# 1-Schematic_RpiZeroKeyboard.net
KiCad netlist of a schematic drawn in EasyEDA
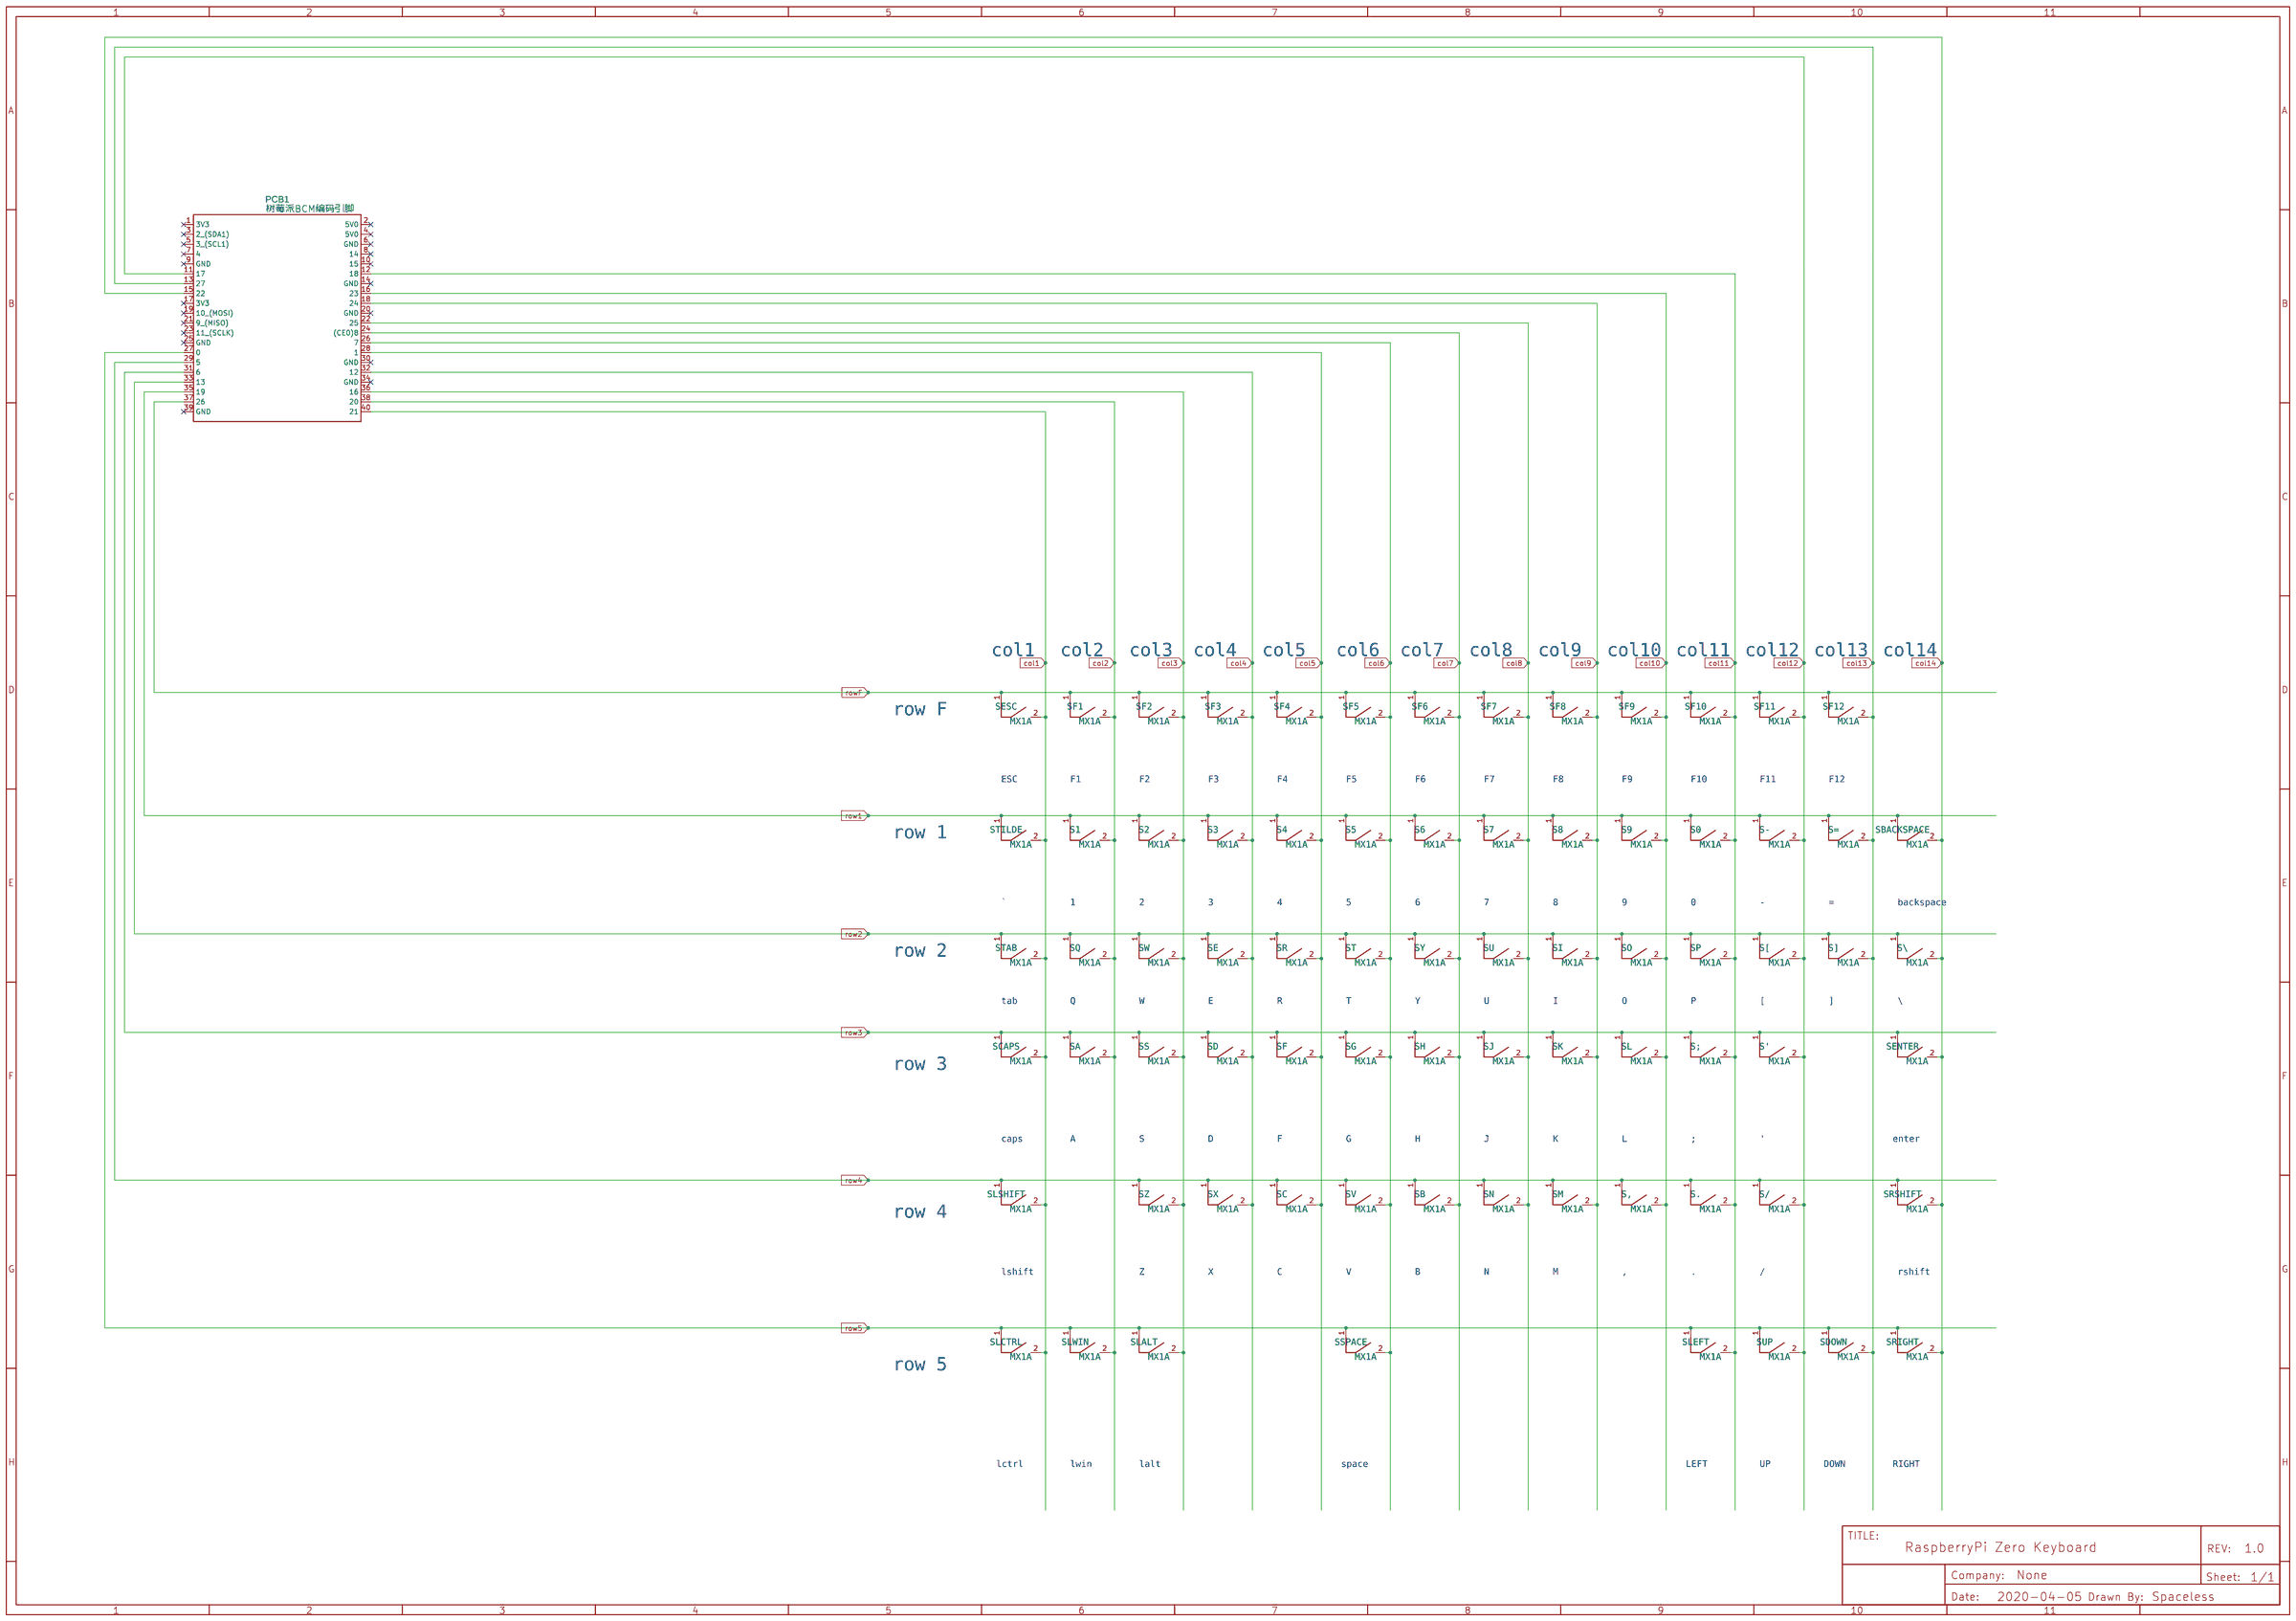
[diagram p0: schematic sheet]

(export (version "E")
  (design (tool "Eeschema 10.0.6"))
  (components
    (comp (ref "PCB1") (value "树莓派BCM编码引脚") (libsource (lib "") (part "树莓派 zero w BCM编码引脚")))
    (comp (ref "S'") (value "MX1A") (libsource (lib "") (part "Unknown_1800_275")))
    (comp (ref "S,") (value "MX1A") (libsource (lib "") (part "Unknown_1660_425")))
    (comp (ref "S-") (value "MX1A") (libsource (lib "") (part "Unknown_1800_55")))
    (comp (ref "S.") (value "MX1A") (libsource (lib "") (part "Unknown_1730_425")))
    (comp (ref "S/") (value "MX1A") (libsource (lib "") (part "Unknown_1800_425")))
    (comp (ref "S0") (value "MX1A") (libsource (lib "") (part "Unknown_1730_55")))
    (comp (ref "S1") (value "MX1A") (libsource (lib "") (part "Unknown_1100_55")))
    (comp (ref "S2") (value "MX1A") (libsource (lib "") (part "Unknown_1170_55")))
    (comp (ref "S3") (value "MX1A") (libsource (lib "") (part "Unknown_1240_55")))
    (comp (ref "S4") (value "MX1A") (libsource (lib "") (part "Unknown_1310_55")))
    (comp (ref "S5") (value "MX1A") (libsource (lib "") (part "Unknown_1380_55")))
    (comp (ref "S6") (value "MX1A") (libsource (lib "") (part "Unknown_1450_55")))
    (comp (ref "S7") (value "MX1A") (libsource (lib "") (part "Unknown_1520_55")))
    (comp (ref "S8") (value "MX1A") (libsource (lib "") (part "Unknown_1590_55")))
    (comp (ref "S9") (value "MX1A") (libsource (lib "") (part "Unknown_1660_55")))
    (comp (ref "S;") (value "MX1A") (libsource (lib "") (part "Unknown_1730_275")))
    (comp (ref "S=") (value "MX1A") (libsource (lib "") (part "Unknown_1870_55")))
    (comp (ref "SA") (value "MX1A") (libsource (lib "") (part "Unknown_1100_275")))
    (comp (ref "SB") (value "MX1A") (libsource (lib "") (part "Unknown_1450_425")))
    (comp (ref "SBACKSPACE") (value "MX1A") (libsource (lib "") (part "Unknown_1940_55")))
    (comp (ref "SC") (value "MX1A") (libsource (lib "") (part "Unknown_1310_425")))
    (comp (ref "SCAPS") (value "MX1A") (libsource (lib "") (part "Unknown_1030_275")))
    (comp (ref "SD") (value "MX1A") (libsource (lib "") (part "Unknown_1240_275")))
    (comp (ref "SDOWN") (value "MX1A") (libsource (lib "") (part "Unknown_1870_575")))
    (comp (ref "SE") (value "MX1A") (libsource (lib "") (part "Unknown_1240_175")))
    (comp (ref "SENTER") (value "MX1A") (libsource (lib "") (part "Unknown_1940_275")))
    (comp (ref "SESC") (value "MX1A") (libsource (lib "") (part "Unknown_1030_-70")))
    (comp (ref "SF") (value "MX1A") (libsource (lib "") (part "Unknown_1310_275")))
    (comp (ref "SF1") (value "MX1A") (libsource (lib "") (part "Unknown_1100_-70")))
    (comp (ref "SF2") (value "MX1A") (libsource (lib "") (part "Unknown_1170_-70")))
    (comp (ref "SF3") (value "MX1A") (libsource (lib "") (part "Unknown_1240_-70")))
    (comp (ref "SF4") (value "MX1A") (libsource (lib "") (part "Unknown_1310_-70")))
    (comp (ref "SF5") (value "MX1A") (libsource (lib "") (part "Unknown_1380_-70")))
    (comp (ref "SF6") (value "MX1A") (libsource (lib "") (part "Unknown_1450_-70")))
    (comp (ref "SF7") (value "MX1A") (libsource (lib "") (part "Unknown_1520_-70")))
    (comp (ref "SF8") (value "MX1A") (libsource (lib "") (part "Unknown_1590_-70")))
    (comp (ref "SF9") (value "MX1A") (libsource (lib "") (part "Unknown_1660_-70")))
    (comp (ref "SF10") (value "MX1A") (libsource (lib "") (part "Unknown_1730_-70")))
    (comp (ref "SF11") (value "MX1A") (libsource (lib "") (part "Unknown_1800_-70")))
    (comp (ref "SF12") (value "MX1A") (libsource (lib "") (part "Unknown_1870_-70")))
    (comp (ref "SG") (value "MX1A") (libsource (lib "") (part "Unknown_1380_275")))
    (comp (ref "SH") (value "MX1A") (libsource (lib "") (part "Unknown_1450_275")))
    (comp (ref "SI") (value "MX1A") (libsource (lib "") (part "Unknown_1590_175")))
    (comp (ref "SJ") (value "MX1A") (libsource (lib "") (part "Unknown_1520_275")))
    (comp (ref "SK") (value "MX1A") (libsource (lib "") (part "Unknown_1590_275")))
    (comp (ref "SL") (value "MX1A") (libsource (lib "") (part "Unknown_1660_275")))
    (comp (ref "SLALT") (value "MX1A") (libsource (lib "") (part "Unknown_1170_575")))
    (comp (ref "SLCTRL") (value "MX1A") (libsource (lib "") (part "Unknown_1030_575")))
    (comp (ref "SLEFT") (value "MX1A") (libsource (lib "") (part "Unknown_1730_575")))
    (comp (ref "SLSHIFT") (value "MX1A") (libsource (lib "") (part "Unknown_1030_425")))
    (comp (ref "SLWIN") (value "MX1A") (libsource (lib "") (part "Unknown_1100_575")))
    (comp (ref "SM") (value "MX1A") (libsource (lib "") (part "Unknown_1590_425")))
    (comp (ref "SN") (value "MX1A") (libsource (lib "") (part "Unknown_1520_425")))
    (comp (ref "SO") (value "MX1A") (libsource (lib "") (part "Unknown_1660_175")))
    (comp (ref "SP") (value "MX1A") (libsource (lib "") (part "Unknown_1730_175")))
    (comp (ref "SQ") (value "MX1A") (libsource (lib "") (part "Unknown_1100_175")))
    (comp (ref "SR") (value "MX1A") (libsource (lib "") (part "Unknown_1310_175")))
    (comp (ref "SRIGHT") (value "MX1A") (libsource (lib "") (part "Unknown_1940_575")))
    (comp (ref "SRSHIFT") (value "MX1A") (libsource (lib "") (part "Unknown_1940_425")))
    (comp (ref "SS") (value "MX1A") (libsource (lib "") (part "Unknown_1170_275")))
    (comp (ref "SSPACE") (value "MX1A") (libsource (lib "") (part "Unknown_1380_575")))
    (comp (ref "ST") (value "MX1A") (libsource (lib "") (part "Unknown_1380_175")))
    (comp (ref "STAB") (value "MX1A") (libsource (lib "") (part "Unknown_1030_175")))
    (comp (ref "STILDE") (value "MX1A") (libsource (lib "") (part "Unknown_1030_55")))
    (comp (ref "SU") (value "MX1A") (libsource (lib "") (part "Unknown_1520_175")))
    (comp (ref "SUP") (value "MX1A") (libsource (lib "") (part "Unknown_1800_575")))
    (comp (ref "SV") (value "MX1A") (libsource (lib "") (part "Unknown_1380_425")))
    (comp (ref "SW") (value "MX1A") (libsource (lib "") (part "Unknown_1170_175")))
    (comp (ref "SX") (value "MX1A") (libsource (lib "") (part "Unknown_1240_425")))
    (comp (ref "SY") (value "MX1A") (libsource (lib "") (part "Unknown_1450_175")))
    (comp (ref "SZ") (value "MX1A") (libsource (lib "") (part "Unknown_1170_425")))
    (comp (ref "S[") (value "MX1A") (libsource (lib "") (part "Unknown_1800_175")))
    (comp (ref "S\\") (value "MX1A") (libsource (lib "") (part "Unknown_1940_175")))
    (comp (ref "S]") (value "MX1A") (libsource (lib "") (part "Unknown_1870_175")))
  )
  (nets
    (net (code "1") (name "col1") (class "Default")
      (node (ref "PCB1") (pin "40") (pinfunction "21_40") (pintype "unspecified"))
      (node (ref "SCAPS") (pin "2") (pintype "unspecified"))
      (node (ref "SESC") (pin "2") (pintype "unspecified"))
      (node (ref "SLCTRL") (pin "2") (pintype "unspecified"))
      (node (ref "SLSHIFT") (pin "2") (pintype "unspecified"))
      (node (ref "STAB") (pin "2") (pintype "unspecified"))
      (node (ref "STILDE") (pin "2") (pintype "unspecified"))
    )
    (net (code "2") (name "col2") (class "Default")
      (node (ref "PCB1") (pin "38") (pinfunction "20_38") (pintype "unspecified"))
      (node (ref "S1") (pin "2") (pintype "unspecified"))
      (node (ref "SA") (pin "2") (pintype "unspecified"))
      (node (ref "SF1") (pin "2") (pintype "unspecified"))
      (node (ref "SLWIN") (pin "2") (pintype "unspecified"))
      (node (ref "SQ") (pin "2") (pintype "unspecified"))
    )
    (net (code "3") (name "col3") (class "Default")
      (node (ref "PCB1") (pin "36") (pinfunction "16_36") (pintype "unspecified"))
      (node (ref "S2") (pin "2") (pintype "unspecified"))
      (node (ref "SF2") (pin "2") (pintype "unspecified"))
      (node (ref "SLALT") (pin "2") (pintype "unspecified"))
      (node (ref "SS") (pin "2") (pintype "unspecified"))
      (node (ref "SW") (pin "2") (pintype "unspecified"))
      (node (ref "SZ") (pin "2") (pintype "unspecified"))
    )
    (net (code "4") (name "col4") (class "Default")
      (node (ref "PCB1") (pin "32") (pinfunction "12_32") (pintype "unspecified"))
      (node (ref "S3") (pin "2") (pintype "unspecified"))
      (node (ref "SD") (pin "2") (pintype "unspecified"))
      (node (ref "SE") (pin "2") (pintype "unspecified"))
      (node (ref "SF3") (pin "2") (pintype "unspecified"))
      (node (ref "SX") (pin "2") (pintype "unspecified"))
    )
    (net (code "5") (name "col5") (class "Default")
      (node (ref "PCB1") (pin "28") (pinfunction "1_28") (pintype "unspecified"))
      (node (ref "S4") (pin "2") (pintype "unspecified"))
      (node (ref "SC") (pin "2") (pintype "unspecified"))
      (node (ref "SF") (pin "2") (pintype "unspecified"))
      (node (ref "SF4") (pin "2") (pintype "unspecified"))
      (node (ref "SR") (pin "2") (pintype "unspecified"))
    )
    (net (code "6") (name "col6") (class "Default")
      (node (ref "PCB1") (pin "26") (pinfunction "7_26") (pintype "unspecified"))
      (node (ref "S5") (pin "2") (pintype "unspecified"))
      (node (ref "SF5") (pin "2") (pintype "unspecified"))
      (node (ref "SG") (pin "2") (pintype "unspecified"))
      (node (ref "SSPACE") (pin "2") (pintype "unspecified"))
      (node (ref "ST") (pin "2") (pintype "unspecified"))
      (node (ref "SV") (pin "2") (pintype "unspecified"))
    )
    (net (code "7") (name "col7") (class "Default")
      (node (ref "PCB1") (pin "24") (pinfunction "(CE0)8_24") (pintype "unspecified"))
      (node (ref "S6") (pin "2") (pintype "unspecified"))
      (node (ref "SB") (pin "2") (pintype "unspecified"))
      (node (ref "SF6") (pin "2") (pintype "unspecified"))
      (node (ref "SH") (pin "2") (pintype "unspecified"))
      (node (ref "SY") (pin "2") (pintype "unspecified"))
    )
    (net (code "8") (name "col8") (class "Default")
      (node (ref "PCB1") (pin "22") (pinfunction "25_22") (pintype "unspecified"))
      (node (ref "S7") (pin "2") (pintype "unspecified"))
      (node (ref "SF7") (pin "2") (pintype "unspecified"))
      (node (ref "SJ") (pin "2") (pintype "unspecified"))
      (node (ref "SN") (pin "2") (pintype "unspecified"))
      (node (ref "SU") (pin "2") (pintype "unspecified"))
    )
    (net (code "9") (name "col9") (class "Default")
      (node (ref "PCB1") (pin "18") (pinfunction "24_18") (pintype "unspecified"))
      (node (ref "S8") (pin "2") (pintype "unspecified"))
      (node (ref "SF8") (pin "2") (pintype "unspecified"))
      (node (ref "SI") (pin "2") (pintype "unspecified"))
      (node (ref "SK") (pin "2") (pintype "unspecified"))
      (node (ref "SM") (pin "2") (pintype "unspecified"))
    )
    (net (code "10") (name "col10") (class "Default")
      (node (ref "PCB1") (pin "16") (pinfunction "23_16") (pintype "unspecified"))
      (node (ref "S,") (pin "2") (pintype "unspecified"))
      (node (ref "S9") (pin "2") (pintype "unspecified"))
      (node (ref "SF9") (pin "2") (pintype "unspecified"))
      (node (ref "SL") (pin "2") (pintype "unspecified"))
      (node (ref "SO") (pin "2") (pintype "unspecified"))
    )
    (net (code "11") (name "col11") (class "Default")
      (node (ref "PCB1") (pin "12") (pinfunction "18_12") (pintype "unspecified"))
      (node (ref "S.") (pin "2") (pintype "unspecified"))
      (node (ref "S0") (pin "2") (pintype "unspecified"))
      (node (ref "S;") (pin "2") (pintype "unspecified"))
      (node (ref "SF10") (pin "2") (pintype "unspecified"))
      (node (ref "SLEFT") (pin "2") (pintype "unspecified"))
      (node (ref "SP") (pin "2") (pintype "unspecified"))
    )
    (net (code "12") (name "col12") (class "Default")
      (node (ref "PCB1") (pin "11") (pinfunction "17_11") (pintype "unspecified"))
      (node (ref "S'") (pin "2") (pintype "unspecified"))
      (node (ref "S-") (pin "2") (pintype "unspecified"))
      (node (ref "S/") (pin "2") (pintype "unspecified"))
      (node (ref "SF11") (pin "2") (pintype "unspecified"))
      (node (ref "SUP") (pin "2") (pintype "unspecified"))
      (node (ref "S[") (pin "2") (pintype "unspecified"))
    )
    (net (code "13") (name "col13") (class "Default")
      (node (ref "PCB1") (pin "13") (pinfunction "27_13") (pintype "unspecified"))
      (node (ref "S=") (pin "2") (pintype "unspecified"))
      (node (ref "SDOWN") (pin "2") (pintype "unspecified"))
      (node (ref "SF12") (pin "2") (pintype "unspecified"))
      (node (ref "S]") (pin "2") (pintype "unspecified"))
    )
    (net (code "14") (name "col14") (class "Default")
      (node (ref "PCB1") (pin "15") (pinfunction "22_15") (pintype "unspecified"))
      (node (ref "SBACKSPACE") (pin "2") (pintype "unspecified"))
      (node (ref "SENTER") (pin "2") (pintype "unspecified"))
      (node (ref "SRIGHT") (pin "2") (pintype "unspecified"))
      (node (ref "SRSHIFT") (pin "2") (pintype "unspecified"))
      (node (ref "S\\") (pin "2") (pintype "unspecified"))
    )
    (net (code "15") (name "row1") (class "Default")
      (node (ref "PCB1") (pin "35") (pinfunction "19_35") (pintype "unspecified"))
      (node (ref "S-") (pin "1") (pintype "unspecified"))
      (node (ref "S0") (pin "1") (pintype "unspecified"))
      (node (ref "S1") (pin "1") (pintype "unspecified"))
      (node (ref "S2") (pin "1") (pintype "unspecified"))
      (node (ref "S3") (pin "1") (pintype "unspecified"))
      (node (ref "S4") (pin "1") (pintype "unspecified"))
      (node (ref "S5") (pin "1") (pintype "unspecified"))
      (node (ref "S6") (pin "1") (pintype "unspecified"))
      (node (ref "S7") (pin "1") (pintype "unspecified"))
      (node (ref "S8") (pin "1") (pintype "unspecified"))
      (node (ref "S9") (pin "1") (pintype "unspecified"))
      (node (ref "S=") (pin "1") (pintype "unspecified"))
      (node (ref "SBACKSPACE") (pin "1") (pintype "unspecified"))
      (node (ref "STILDE") (pin "1") (pintype "unspecified"))
    )
    (net (code "16") (name "row2") (class "Default")
      (node (ref "PCB1") (pin "33") (pinfunction "13_33") (pintype "unspecified"))
      (node (ref "SE") (pin "1") (pintype "unspecified"))
      (node (ref "SI") (pin "1") (pintype "unspecified"))
      (node (ref "SO") (pin "1") (pintype "unspecified"))
      (node (ref "SP") (pin "1") (pintype "unspecified"))
      (node (ref "SQ") (pin "1") (pintype "unspecified"))
      (node (ref "SR") (pin "1") (pintype "unspecified"))
      (node (ref "ST") (pin "1") (pintype "unspecified"))
      (node (ref "STAB") (pin "1") (pintype "unspecified"))
      (node (ref "SU") (pin "1") (pintype "unspecified"))
      (node (ref "SW") (pin "1") (pintype "unspecified"))
      (node (ref "SY") (pin "1") (pintype "unspecified"))
      (node (ref "S[") (pin "1") (pintype "unspecified"))
      (node (ref "S\\") (pin "1") (pintype "unspecified"))
      (node (ref "S]") (pin "1") (pintype "unspecified"))
    )
    (net (code "17") (name "row3") (class "Default")
      (node (ref "PCB1") (pin "31") (pinfunction "6_31") (pintype "unspecified"))
      (node (ref "S'") (pin "1") (pintype "unspecified"))
      (node (ref "S;") (pin "1") (pintype "unspecified"))
      (node (ref "SA") (pin "1") (pintype "unspecified"))
      (node (ref "SCAPS") (pin "1") (pintype "unspecified"))
      (node (ref "SD") (pin "1") (pintype "unspecified"))
      (node (ref "SENTER") (pin "1") (pintype "unspecified"))
      (node (ref "SF") (pin "1") (pintype "unspecified"))
      (node (ref "SG") (pin "1") (pintype "unspecified"))
      (node (ref "SH") (pin "1") (pintype "unspecified"))
      (node (ref "SJ") (pin "1") (pintype "unspecified"))
      (node (ref "SK") (pin "1") (pintype "unspecified"))
      (node (ref "SL") (pin "1") (pintype "unspecified"))
      (node (ref "SS") (pin "1") (pintype "unspecified"))
    )
    (net (code "18") (name "row4") (class "Default")
      (node (ref "PCB1") (pin "29") (pinfunction "5_29") (pintype "unspecified"))
      (node (ref "S,") (pin "1") (pintype "unspecified"))
      (node (ref "S.") (pin "1") (pintype "unspecified"))
      (node (ref "S/") (pin "1") (pintype "unspecified"))
      (node (ref "SB") (pin "1") (pintype "unspecified"))
      (node (ref "SC") (pin "1") (pintype "unspecified"))
      (node (ref "SLSHIFT") (pin "1") (pintype "unspecified"))
      (node (ref "SM") (pin "1") (pintype "unspecified"))
      (node (ref "SN") (pin "1") (pintype "unspecified"))
      (node (ref "SRSHIFT") (pin "1") (pintype "unspecified"))
      (node (ref "SV") (pin "1") (pintype "unspecified"))
      (node (ref "SX") (pin "1") (pintype "unspecified"))
      (node (ref "SZ") (pin "1") (pintype "unspecified"))
    )
    (net (code "19") (name "row5") (class "Default")
      (node (ref "PCB1") (pin "27") (pinfunction "0_27") (pintype "unspecified"))
      (node (ref "SDOWN") (pin "1") (pintype "unspecified"))
      (node (ref "SLALT") (pin "1") (pintype "unspecified"))
      (node (ref "SLCTRL") (pin "1") (pintype "unspecified"))
      (node (ref "SLEFT") (pin "1") (pintype "unspecified"))
      (node (ref "SLWIN") (pin "1") (pintype "unspecified"))
      (node (ref "SRIGHT") (pin "1") (pintype "unspecified"))
      (node (ref "SSPACE") (pin "1") (pintype "unspecified"))
      (node (ref "SUP") (pin "1") (pintype "unspecified"))
    )
    (net (code "20") (name "rowF") (class "Default")
      (node (ref "PCB1") (pin "37") (pinfunction "26_37") (pintype "unspecified"))
      (node (ref "SESC") (pin "1") (pintype "unspecified"))
      (node (ref "SF1") (pin "1") (pintype "unspecified"))
      (node (ref "SF10") (pin "1") (pintype "unspecified"))
      (node (ref "SF11") (pin "1") (pintype "unspecified"))
      (node (ref "SF12") (pin "1") (pintype "unspecified"))
      (node (ref "SF2") (pin "1") (pintype "unspecified"))
      (node (ref "SF3") (pin "1") (pintype "unspecified"))
      (node (ref "SF4") (pin "1") (pintype "unspecified"))
      (node (ref "SF5") (pin "1") (pintype "unspecified"))
      (node (ref "SF6") (pin "1") (pintype "unspecified"))
      (node (ref "SF7") (pin "1") (pintype "unspecified"))
      (node (ref "SF8") (pin "1") (pintype "unspecified"))
      (node (ref "SF9") (pin "1") (pintype "unspecified"))
    )
    (net (code "21") (name "unconnected-(PCB1-2_(SDA1)-Pad3)") (class "Default")
      (node (ref "PCB1") (pin "3") (pinfunction "2_(SDA1)_3") (pintype "unspecified+no_connect"))
    )
    (net (code "22") (name "unconnected-(PCB1-3V3-Pad1)") (class "Default")
      (node (ref "PCB1") (pin "1") (pinfunction "3V3_1") (pintype "unspecified+no_connect"))
    )
    (net (code "23") (name "unconnected-(PCB1-3V3-Pad17)") (class "Default")
      (node (ref "PCB1") (pin "17") (pinfunction "3V3_17") (pintype "unspecified+no_connect"))
    )
    (net (code "24") (name "unconnected-(PCB1-3_(SCL1)-Pad5)") (class "Default")
      (node (ref "PCB1") (pin "5") (pinfunction "3_(SCL1)_5") (pintype "unspecified+no_connect"))
    )
    (net (code "25") (name "unconnected-(PCB1-4-Pad7)") (class "Default")
      (node (ref "PCB1") (pin "7") (pinfunction "4_7") (pintype "unspecified+no_connect"))
    )
    (net (code "26") (name "unconnected-(PCB1-5V0-Pad2)") (class "Default")
      (node (ref "PCB1") (pin "2") (pinfunction "5V0_2") (pintype "unspecified+no_connect"))
    )
    (net (code "27") (name "unconnected-(PCB1-5V0-Pad4)") (class "Default")
      (node (ref "PCB1") (pin "4") (pinfunction "5V0_4") (pintype "unspecified+no_connect"))
    )
    (net (code "28") (name "unconnected-(PCB1-9_(MISO)-Pad21)") (class "Default")
      (node (ref "PCB1") (pin "21") (pinfunction "9_(MISO)_21") (pintype "unspecified+no_connect"))
    )
    (net (code "29") (name "unconnected-(PCB1-10_(MOSI)-Pad19)") (class "Default")
      (node (ref "PCB1") (pin "19") (pinfunction "10_(MOSI)_19") (pintype "unspecified+no_connect"))
    )
    (net (code "30") (name "unconnected-(PCB1-11_(SCLK)-Pad23)") (class "Default")
      (node (ref "PCB1") (pin "23") (pinfunction "11_(SCLK)_23") (pintype "unspecified+no_connect"))
    )
    (net (code "31") (name "unconnected-(PCB1-14-Pad8)") (class "Default")
      (node (ref "PCB1") (pin "8") (pinfunction "14_8") (pintype "unspecified+no_connect"))
    )
    (net (code "32") (name "unconnected-(PCB1-15-Pad10)") (class "Default")
      (node (ref "PCB1") (pin "10") (pinfunction "15_10") (pintype "unspecified+no_connect"))
    )
    (net (code "33") (name "unconnected-(PCB1-GND-Pad6)") (class "Default")
      (node (ref "PCB1") (pin "6") (pinfunction "GND_6") (pintype "unspecified+no_connect"))
    )
    (net (code "34") (name "unconnected-(PCB1-GND-Pad9)") (class "Default")
      (node (ref "PCB1") (pin "9") (pinfunction "GND_9") (pintype "unspecified+no_connect"))
    )
    (net (code "35") (name "unconnected-(PCB1-GND-Pad14)") (class "Default")
      (node (ref "PCB1") (pin "14") (pinfunction "GND_14") (pintype "unspecified+no_connect"))
    )
    (net (code "36") (name "unconnected-(PCB1-GND-Pad20)") (class "Default")
      (node (ref "PCB1") (pin "20") (pinfunction "GND_20") (pintype "unspecified+no_connect"))
    )
    (net (code "37") (name "unconnected-(PCB1-GND-Pad25)") (class "Default")
      (node (ref "PCB1") (pin "25") (pinfunction "GND_25") (pintype "unspecified+no_connect"))
    )
    (net (code "38") (name "unconnected-(PCB1-GND-Pad30)") (class "Default")
      (node (ref "PCB1") (pin "30") (pinfunction "GND_30") (pintype "unspecified+no_connect"))
    )
    (net (code "39") (name "unconnected-(PCB1-GND-Pad34)") (class "Default")
      (node (ref "PCB1") (pin "34") (pinfunction "GND_34") (pintype "unspecified+no_connect"))
    )
    (net (code "40") (name "unconnected-(PCB1-GND-Pad39)") (class "Default")
      (node (ref "PCB1") (pin "39") (pinfunction "GND_39") (pintype "unspecified+no_connect"))
    )
  )
)
